# T-11_Version_6.net
KiCad netlist of a schematic drawn in EAGLE
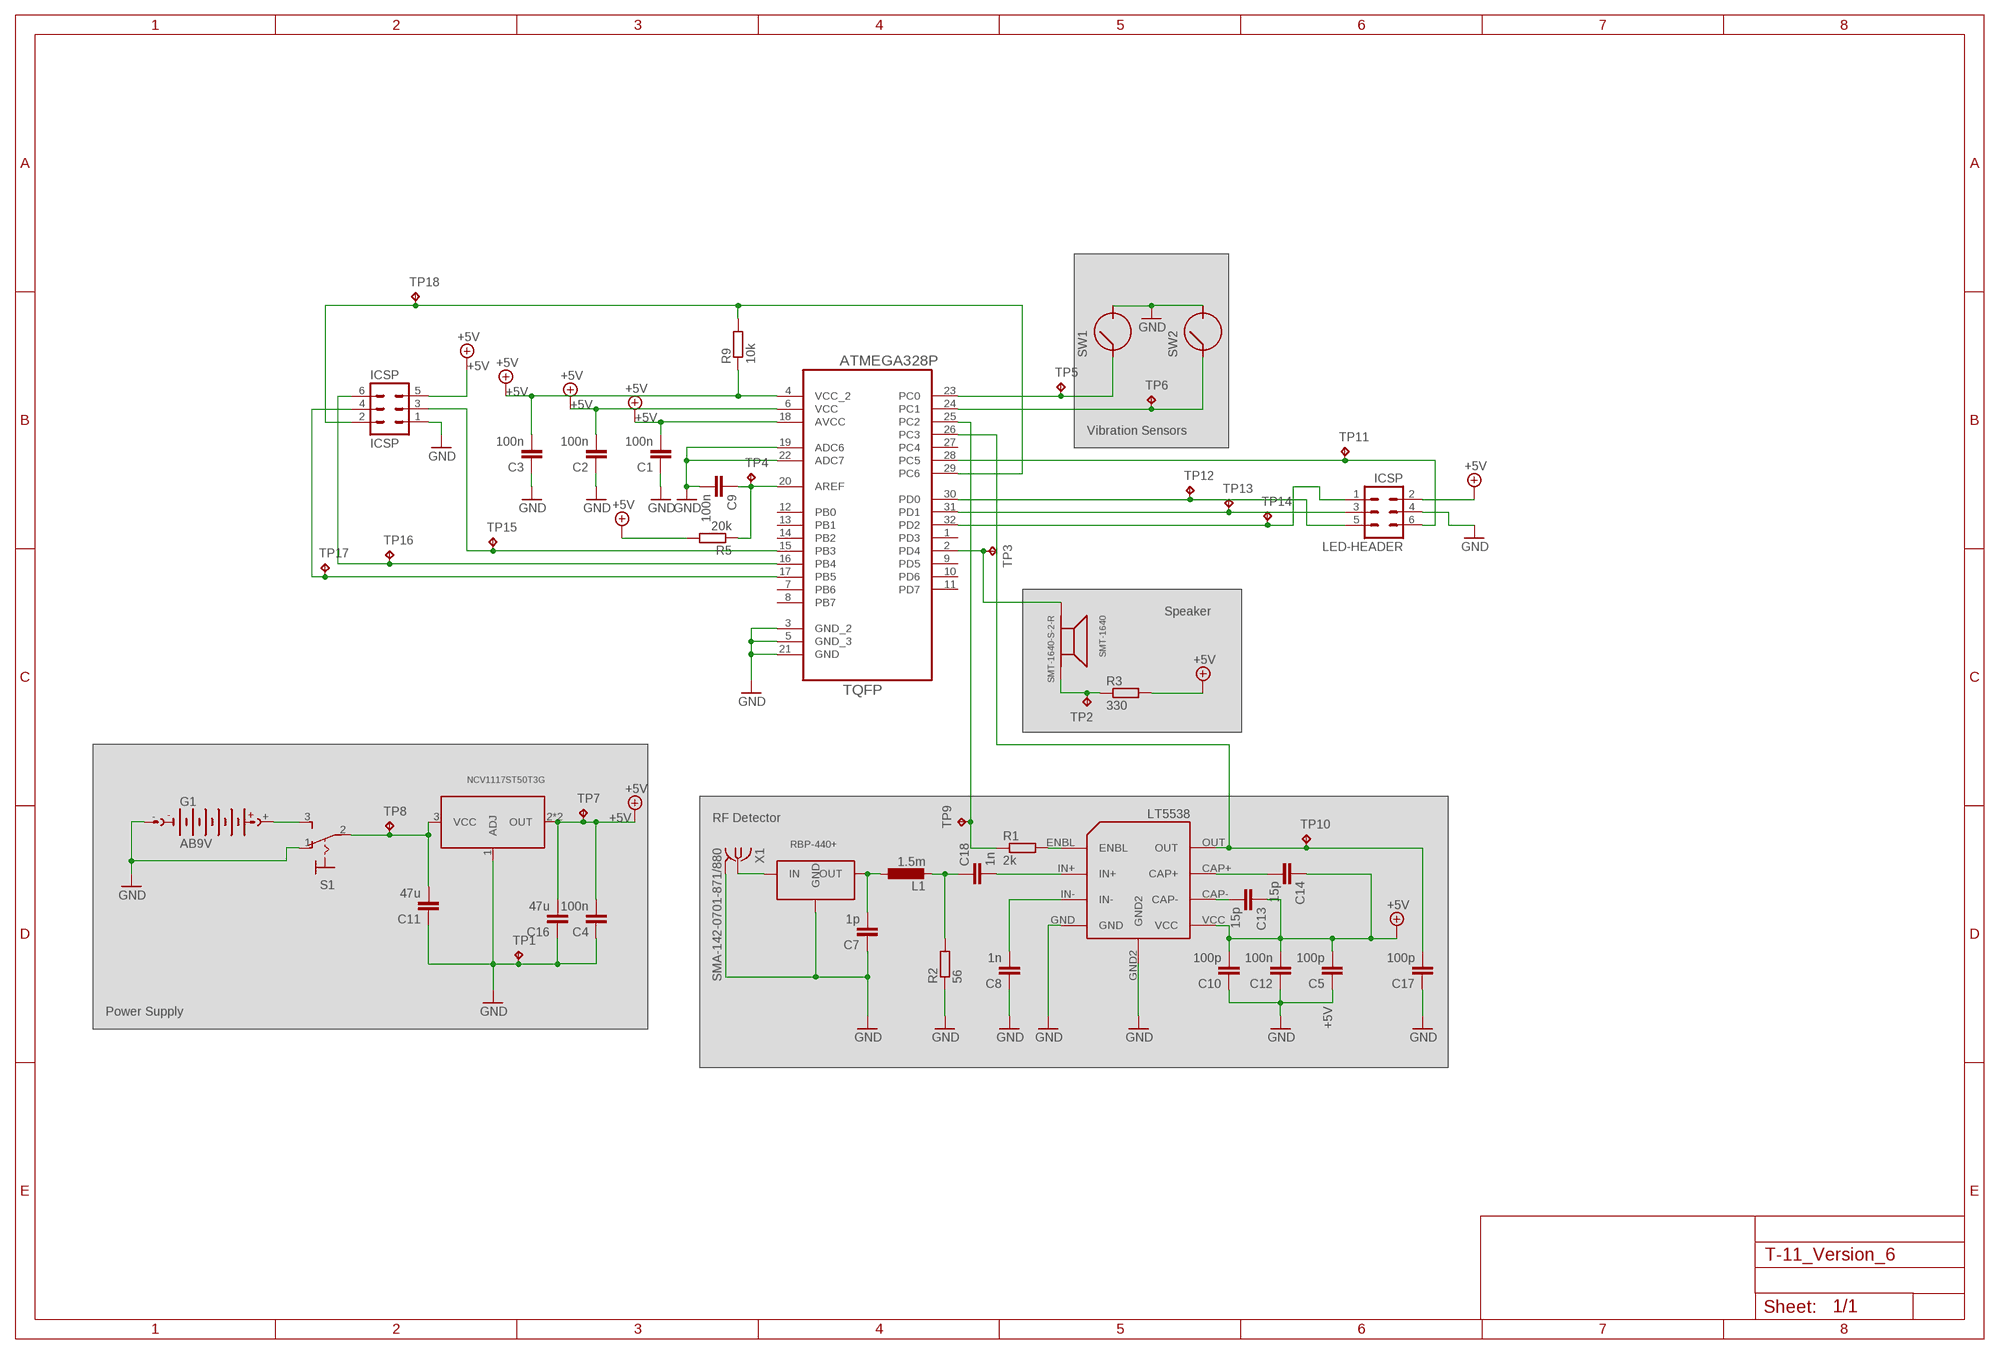
[diagram p0: schematic, sheet 1]

(export (version "E")
  (design (tool "Eeschema 10.0.6"))
  (components
    (comp (ref "C1")
      (value "100n")
      (footprint "eagle-import:C0805")
      (libsource (lib "eagle-import") (part "C-EUC0805"))
    )
    (comp (ref "C2")
      (value "100n")
      (footprint "eagle-import:C0805")
      (libsource (lib "eagle-import") (part "C-EUC0805"))
    )
    (comp (ref "C3")
      (value "100n")
      (footprint "eagle-import:C0805")
      (libsource (lib "eagle-import") (part "C-EUC0805"))
    )
    (comp (ref "C4")
      (value "100n")
      (footprint "eagle-import:C0805")
      (libsource (lib "eagle-import") (part "C-EUC0805"))
    )
    (comp (ref "C5")
      (value "100p")
      (footprint "eagle-import:C0805")
      (libsource (lib "eagle-import") (part "C-EUC0805"))
    )
    (comp (ref "C7")
      (value "1p")
      (footprint "eagle-import:C0805")
      (libsource (lib "eagle-import") (part "C-EUC0805"))
    )
    (comp (ref "C8")
      (value "1n")
      (footprint "eagle-import:C0805")
      (libsource (lib "eagle-import") (part "C-EUC0805"))
    )
    (comp (ref "C9")
      (value "100n")
      (footprint "eagle-import:C0805")
      (libsource (lib "eagle-import") (part "C-EUC0805"))
    )
    (comp (ref "C10")
      (value "100p")
      (footprint "eagle-import:C0805")
      (libsource (lib "eagle-import") (part "C-EUC0805"))
    )
    (comp (ref "C11")
      (value "47u")
      (footprint "eagle-import:C0805")
      (libsource (lib "eagle-import") (part "C-EUC0805"))
    )
    (comp (ref "C12")
      (value "100n")
      (footprint "eagle-import:C0805")
      (libsource (lib "eagle-import") (part "C-EUC0805"))
    )
    (comp (ref "C13")
      (value "15p")
      (footprint "eagle-import:C0805")
      (libsource (lib "eagle-import") (part "C-EUC0805"))
    )
    (comp (ref "C14")
      (value "15p")
      (footprint "eagle-import:C0805")
      (libsource (lib "eagle-import") (part "C-EUC0805"))
    )
    (comp (ref "C16")
      (value "47u")
      (footprint "eagle-import:C0805")
      (libsource (lib "eagle-import") (part "C-EUC0805"))
    )
    (comp (ref "C17")
      (value "100p")
      (footprint "eagle-import:C0805")
      (libsource (lib "eagle-import") (part "C-EUC0805"))
    )
    (comp (ref "C18")
      (value "1n")
      (footprint "eagle-import:C0805")
      (libsource (lib "eagle-import") (part "C-EUC0805"))
    )
    (comp (ref "G1")
      (value "AB9V")
      (footprint "eagle-import:AB9V")
      (libsource (lib "eagle-import") (part "AB9V"))
    )
    (comp (ref "ICSP")
      (value "ICSP")
      (footprint "eagle-import:MA03-2")
      (libsource (lib "eagle-import") (part "MA03-2"))
    )
    (comp (ref "L1")
      (value "1.5m")
      (footprint "eagle-import:L2825P")
      (libsource (lib "eagle-import") (part "L-EUL2825P"))
    )
    (comp (ref "LED-HEADER")
      (value "ICSP")
      (footprint "eagle-import:MA03-2")
      (libsource (lib "eagle-import") (part "MA03-2"))
    )
    (comp (ref "LT5538")
      (value "LT5538")
      (footprint "eagle-import:LT5538")
      (libsource (lib "eagle-import") (part "LT5538"))
    )
    (comp (ref "NVC1")
      (value "NCV1117ST50T3G")
      (footprint "eagle-import:SOT223")
      (libsource (lib "eagle-import") (part "NCV1117ST50T3G"))
    )
    (comp (ref "R1")
      (value "2k")
      (footprint "eagle-import:R0805")
      (libsource (lib "eagle-import") (part "R-EU_R0805"))
    )
    (comp (ref "R2")
      (value "56")
      (footprint "eagle-import:R0805")
      (libsource (lib "eagle-import") (part "R-EU_R0805"))
    )
    (comp (ref "R3")
      (value "330")
      (footprint "eagle-import:R0805")
      (libsource (lib "eagle-import") (part "R-EU_R0805"))
    )
    (comp (ref "R5")
      (value "20k")
      (footprint "eagle-import:R0805")
      (libsource (lib "eagle-import") (part "R-EU_R0805"))
    )
    (comp (ref "R9")
      (value "10k")
      (footprint "eagle-import:R0805")
      (libsource (lib "eagle-import") (part "R-EU_R0805"))
    )
    (comp (ref "RBP-440+")
      (value "RBP-440+")
      (footprint "eagle-import:GP731")
      (libsource (lib "eagle-import") (part "RBP-440+"))
    )
    (comp (ref "S1")
      (value "320-916")
      (footprint "eagle-import:320-916")
      (libsource (lib "eagle-import") (part "320-916"))
    )
    (comp (ref "SMT-1640")
      (value "SMT-1640-S-2-R")
      (footprint "eagle-import:SMT-1640")
      (libsource (lib "eagle-import") (part "SMT-1640-S-2-R"))
    )
    (comp (ref "SW1")
      (value "SW-1801X")
      (footprint "eagle-import:SW-1801X")
      (libsource (lib "eagle-import") (part "SW-1801X"))
    )
    (comp (ref "SW2")
      (value "SW-1801X")
      (footprint "eagle-import:SW-1801X")
      (libsource (lib "eagle-import") (part "SW-1801X"))
    )
    (comp (ref "TP1")
      (value "TPTP10R")
      (footprint "eagle-import:TP10R")
      (libsource (lib "eagle-import") (part "TPTP10R"))
    )
    (comp (ref "TP2")
      (value "TPTP10R")
      (footprint "eagle-import:TP10R")
      (libsource (lib "eagle-import") (part "TPTP10R"))
    )
    (comp (ref "TP3")
      (value "TPTP10R")
      (footprint "eagle-import:TP10R")
      (libsource (lib "eagle-import") (part "TPTP10R"))
    )
    (comp (ref "TP4")
      (value "TPTP10R")
      (footprint "eagle-import:TP10R")
      (libsource (lib "eagle-import") (part "TPTP10R"))
    )
    (comp (ref "TP5")
      (value "TPTP10R")
      (footprint "eagle-import:TP10R")
      (libsource (lib "eagle-import") (part "TPTP10R"))
    )
    (comp (ref "TP6")
      (value "TPTP10R")
      (footprint "eagle-import:TP10R")
      (libsource (lib "eagle-import") (part "TPTP10R"))
    )
    (comp (ref "TP7")
      (value "TPTP10R")
      (footprint "eagle-import:TP10R")
      (libsource (lib "eagle-import") (part "TPTP10R"))
    )
    (comp (ref "TP8")
      (value "TPTP10R")
      (footprint "eagle-import:TP10R")
      (libsource (lib "eagle-import") (part "TPTP10R"))
    )
    (comp (ref "TP9")
      (value "TPTP10R")
      (footprint "eagle-import:TP10R")
      (libsource (lib "eagle-import") (part "TPTP10R"))
    )
    (comp (ref "TP10")
      (value "TPTP10R")
      (footprint "eagle-import:TP10R")
      (libsource (lib "eagle-import") (part "TPTP10R"))
    )
    (comp (ref "TP11")
      (value "TPTP10R")
      (footprint "eagle-import:TP10R")
      (libsource (lib "eagle-import") (part "TPTP10R"))
    )
    (comp (ref "TP12")
      (value "TPTP10R")
      (footprint "eagle-import:TP10R")
      (libsource (lib "eagle-import") (part "TPTP10R"))
    )
    (comp (ref "TP13")
      (value "TPTP10R")
      (footprint "eagle-import:TP10R")
      (libsource (lib "eagle-import") (part "TPTP10R"))
    )
    (comp (ref "TP14")
      (value "TPTP10R")
      (footprint "eagle-import:TP10R")
      (libsource (lib "eagle-import") (part "TPTP10R"))
    )
    (comp (ref "TP15")
      (value "TPTP10R")
      (footprint "eagle-import:TP10R")
      (libsource (lib "eagle-import") (part "TPTP10R"))
    )
    (comp (ref "TP16")
      (value "TPTP10R")
      (footprint "eagle-import:TP10R")
      (libsource (lib "eagle-import") (part "TPTP10R"))
    )
    (comp (ref "TP17")
      (value "TPTP10R")
      (footprint "eagle-import:TP10R")
      (libsource (lib "eagle-import") (part "TPTP10R"))
    )
    (comp (ref "TP18")
      (value "TPTP10R")
      (footprint "eagle-import:TP10R")
      (libsource (lib "eagle-import") (part "TPTP10R"))
    )
    (comp (ref "U1")
      (value "ATMEGA328P-AU")
      (footprint "eagle-import:QFP80P900X900X120-32N")
      (libsource (lib "eagle-import") (part "ATMEGA328P-AU"))
    )
    (comp (ref "X1")
      (value "SMA-142-0701-871/880")
      (footprint "eagle-import:SMA-142-0701-871")
      (fields (field (name "MF") "JOHNSON COMPONENTS") (field (name "MPN") "142-0701-871"))
      (libsource (lib "eagle-import") (part "SMA-142-0701-871/880"))
    )
  )
  (nets
    (net (code "1") (name "+5V") (class "Default")
      (node (ref "C1") (pin "2") (pinfunction "2_2") (pintype "passive"))
      (node (ref "C10") (pin "2") (pinfunction "2_2") (pintype "passive"))
      (node (ref "C12") (pin "2") (pinfunction "2_2") (pintype "passive"))
      (node (ref "C13") (pin "1") (pinfunction "1_1") (pintype "passive"))
      (node (ref "C14") (pin "1") (pinfunction "1_1") (pintype "passive"))
      (node (ref "C16") (pin "2") (pinfunction "2_2") (pintype "passive"))
      (node (ref "C2") (pin "2") (pinfunction "2_2") (pintype "passive"))
      (node (ref "C3") (pin "2") (pinfunction "2_2") (pintype "passive"))
      (node (ref "C4") (pin "2") (pinfunction "2_2") (pintype "passive"))
      (node (ref "C5") (pin "2") (pinfunction "2_2") (pintype "passive"))
      (node (ref "ICSP") (pin "5") (pinfunction "5_5") (pintype "passive"))
      (node (ref "LED-HEADER") (pin "2") (pinfunction "2_2") (pintype "passive"))
      (node (ref "LT5538") (pin "VCC") (pinfunction "VCC_VCC") (pintype "power_in"))
      (node (ref "NVC1") (pin "2") (pinfunction "OUT_2") (pintype "power_in"))
      (node (ref "NVC1") (pin "4") (pinfunction "OUT_4") (pintype "power_in"))
      (node (ref "R3") (pin "2") (pinfunction "2_2") (pintype "passive"))
      (node (ref "R5") (pin "2") (pinfunction "2_2") (pintype "passive"))
      (node (ref "R9") (pin "1") (pinfunction "1_1") (pintype "passive"))
      (node (ref "TP7") (pin "TP") (pinfunction "TP_TP") (pintype "input"))
      (node (ref "U1") (pin "18") (pinfunction "AVCC_18") (pintype "power_in"))
      (node (ref "U1") (pin "4") (pinfunction "VCC_2_4") (pintype "power_in"))
      (node (ref "U1") (pin "6") (pinfunction "VCC_6") (pintype "power_in"))
    )
    (net (code "2") (name "GND") (class "Default")
      (node (ref "C1") (pin "1") (pinfunction "1_1") (pintype "passive"))
      (node (ref "C10") (pin "1") (pinfunction "1_1") (pintype "passive"))
      (node (ref "C11") (pin "1") (pinfunction "1_1") (pintype "passive"))
      (node (ref "C12") (pin "1") (pinfunction "1_1") (pintype "passive"))
      (node (ref "C16") (pin "1") (pinfunction "1_1") (pintype "passive"))
      (node (ref "C17") (pin "1") (pinfunction "1_1") (pintype "passive"))
      (node (ref "C2") (pin "1") (pinfunction "1_1") (pintype "passive"))
      (node (ref "C3") (pin "1") (pinfunction "1_1") (pintype "passive"))
      (node (ref "C4") (pin "1") (pinfunction "1_1") (pintype "passive"))
      (node (ref "C5") (pin "1") (pinfunction "1_1") (pintype "passive"))
      (node (ref "C7") (pin "1") (pinfunction "1_1") (pintype "passive"))
      (node (ref "C8") (pin "1") (pinfunction "1_1") (pintype "passive"))
      (node (ref "C9") (pin "2") (pinfunction "2_2") (pintype "passive"))
      (node (ref "G1") (pin "-") (pinfunction "-_-") (pintype "passive"))
      (node (ref "ICSP") (pin "1") (pinfunction "1_1") (pintype "passive"))
      (node (ref "LED-HEADER") (pin "4") (pinfunction "4_4") (pintype "passive"))
      (node (ref "LT5538") (pin "GND") (pinfunction "GND_GND") (pintype "power_in"))
      (node (ref "LT5538") (pin "GND2") (pinfunction "GND2_GND2") (pintype "bidirectional"))
      (node (ref "NVC1") (pin "1") (pinfunction "ADJ_1") (pintype "bidirectional"))
      (node (ref "R2") (pin "1") (pinfunction "1_1") (pintype "passive"))
      (node (ref "RBP-440+") (pin "1") (pinfunction "GND_1") (pintype "output"))
      (node (ref "RBP-440+") (pin "3") (pinfunction "GND_3") (pintype "output"))
      (node (ref "RBP-440+") (pin "4") (pinfunction "GND_4") (pintype "output"))
      (node (ref "RBP-440+") (pin "5") (pinfunction "GND_5") (pintype "output"))
      (node (ref "RBP-440+") (pin "7") (pinfunction "GND_7") (pintype "output"))
      (node (ref "RBP-440+") (pin "8") (pinfunction "GND_8") (pintype "output"))
      (node (ref "S1") (pin "1") (pinfunction "O_1") (pintype "passive"))
      (node (ref "SW1") (pin "P$2") (pinfunction "P$2_P$2") (pintype "bidirectional"))
      (node (ref "SW2") (pin "P$2") (pinfunction "P$2_P$2") (pintype "bidirectional"))
      (node (ref "TP1") (pin "TP") (pinfunction "TP_TP") (pintype "input"))
      (node (ref "U1") (pin "19") (pinfunction "ADC6_19") (pintype "input"))
      (node (ref "U1") (pin "21") (pinfunction "GND_21") (pintype "passive"))
      (node (ref "U1") (pin "22") (pinfunction "ADC7_22") (pintype "input"))
      (node (ref "U1") (pin "3") (pinfunction "GND_2_3") (pintype "passive"))
      (node (ref "U1") (pin "5") (pinfunction "GND_3_5") (pintype "passive"))
      (node (ref "X1") (pin "2@1") (pinfunction "2_2@1") (pintype "passive"))
      (node (ref "X1") (pin "2@2") (pinfunction "2_2@2") (pintype "passive"))
      (node (ref "X1") (pin "2@3") (pinfunction "2_2@3") (pintype "passive"))
      (node (ref "X1") (pin "2@4") (pinfunction "2_2@4") (pintype "passive"))
    )
    (net (code "3") (name "Net-(C8-Pad2)") (class "Default")
      (node (ref "C8") (pin "2") (pinfunction "2_2") (pintype "passive"))
      (node (ref "LT5538") (pin "IN-") (pinfunction "IN-_IN-") (pintype "bidirectional"))
    )
    (net (code "4") (name "Net-(C13-Pad2)") (class "Default")
      (node (ref "C13") (pin "2") (pinfunction "2_2") (pintype "passive"))
      (node (ref "LT5538") (pin "CAP-") (pinfunction "CAP-_CAP-") (pintype "bidirectional"))
    )
    (net (code "5") (name "Net-(C14-Pad2)") (class "Default")
      (node (ref "C14") (pin "2") (pinfunction "2_2") (pintype "passive"))
      (node (ref "LT5538") (pin "CAP+") (pinfunction "CAP+_CAP+") (pintype "bidirectional"))
    )
    (net (code "6") (name "Net-(C18-Pad1)") (class "Default")
      (node (ref "C18") (pin "1") (pinfunction "1_1") (pintype "passive"))
      (node (ref "L1") (pin "2") (pinfunction "2_2") (pintype "passive"))
      (node (ref "R2") (pin "2") (pinfunction "2_2") (pintype "passive"))
    )
    (net (code "7") (name "Net-(C18-Pad2)") (class "Default")
      (node (ref "C18") (pin "2") (pinfunction "2_2") (pintype "passive"))
      (node (ref "LT5538") (pin "IN+") (pinfunction "IN+_IN+") (pintype "bidirectional"))
    )
    (net (code "8") (name "Net-(LT5538-PadENBL)") (class "Default")
      (node (ref "LT5538") (pin "ENBL") (pinfunction "ENBL_ENBL") (pintype "bidirectional"))
      (node (ref "R1") (pin "2") (pinfunction "2_2") (pintype "passive"))
    )
    (net (code "9") (name "Net-(NVC1-VCC)") (class "Default")
      (node (ref "C11") (pin "2") (pinfunction "2_2") (pintype "passive"))
      (node (ref "NVC1") (pin "3") (pinfunction "VCC_3") (pintype "input"))
      (node (ref "S1") (pin "2") (pinfunction "P_2") (pintype "passive"))
      (node (ref "TP8") (pin "TP") (pinfunction "TP_TP") (pintype "input"))
    )
    (net (code "10") (name "Net-(RBP-440+-IN)") (class "Default")
      (node (ref "RBP-440+") (pin "2") (pinfunction "IN_2") (pintype "bidirectional"))
      (node (ref "X1") (pin "1") (pinfunction "1_1") (pintype "passive"))
    )
    (net (code "11") (name "Net-(RBP-440+-OUT)") (class "Default")
      (node (ref "C7") (pin "2") (pinfunction "2_2") (pintype "passive"))
      (node (ref "L1") (pin "1") (pinfunction "1_1") (pintype "passive"))
      (node (ref "RBP-440+") (pin "6") (pinfunction "OUT_6") (pintype "output"))
    )
    (net (code "12") (name "Net-(S1-S)") (class "Default")
      (node (ref "G1") (pin "+") (pinfunction "+_+") (pintype "passive"))
      (node (ref "S1") (pin "3") (pinfunction "S_3") (pintype "passive"))
    )
    (net (code "13") (name "Net-(SMT-1640-IN)") (class "Default")
      (node (ref "SMT-1640") (pin "P$2") (pinfunction "IN_P$2") (pintype "bidirectional"))
      (node (ref "TP3") (pin "TP") (pinfunction "TP_TP") (pintype "input"))
      (node (ref "U1") (pin "2") (pinfunction "PD4_2") (pintype "bidirectional"))
    )
    (net (code "14") (name "Net-(SMT-1640-OUT)") (class "Default")
      (node (ref "R3") (pin "1") (pinfunction "1_1") (pintype "passive"))
      (node (ref "SMT-1640") (pin "P$1") (pinfunction "OUT_P$1") (pintype "bidirectional"))
      (node (ref "TP2") (pin "TP") (pinfunction "TP_TP") (pintype "input"))
    )
    (net (code "15") (name "Net-(U1-AREF)") (class "Default")
      (node (ref "C9") (pin "1") (pinfunction "1_1") (pintype "passive"))
      (node (ref "R5") (pin "1") (pinfunction "1_1") (pintype "passive"))
      (node (ref "TP4") (pin "TP") (pinfunction "TP_TP") (pintype "input"))
      (node (ref "U1") (pin "20") (pinfunction "AREF_20") (pintype "input"))
    )
    (net (code "16") (name "Net-(U1-PB3)") (class "Default")
      (node (ref "ICSP") (pin "3") (pinfunction "3_3") (pintype "passive"))
      (node (ref "TP15") (pin "TP") (pinfunction "TP_TP") (pintype "input"))
      (node (ref "U1") (pin "15") (pinfunction "PB3_15") (pintype "bidirectional"))
    )
    (net (code "17") (name "Net-(U1-PB4)") (class "Default")
      (node (ref "ICSP") (pin "6") (pinfunction "6_6") (pintype "passive"))
      (node (ref "TP16") (pin "TP") (pinfunction "TP_TP") (pintype "input"))
      (node (ref "U1") (pin "16") (pinfunction "PB4_16") (pintype "bidirectional"))
    )
    (net (code "18") (name "Net-(U1-PB5)") (class "Default")
      (node (ref "ICSP") (pin "4") (pinfunction "4_4") (pintype "passive"))
      (node (ref "TP17") (pin "TP") (pinfunction "TP_TP") (pintype "input"))
      (node (ref "U1") (pin "17") (pinfunction "PB5_17") (pintype "bidirectional"))
    )
    (net (code "19") (name "Net-(U1-PC0)") (class "Default")
      (node (ref "SW1") (pin "P$1") (pinfunction "P$1_P$1") (pintype "bidirectional"))
      (node (ref "TP5") (pin "TP") (pinfunction "TP_TP") (pintype "input"))
      (node (ref "U1") (pin "23") (pinfunction "PC0_23") (pintype "bidirectional"))
    )
    (net (code "20") (name "Net-(U1-PC1)") (class "Default")
      (node (ref "SW2") (pin "P$1") (pinfunction "P$1_P$1") (pintype "bidirectional"))
      (node (ref "TP6") (pin "TP") (pinfunction "TP_TP") (pintype "input"))
      (node (ref "U1") (pin "24") (pinfunction "PC1_24") (pintype "bidirectional"))
    )
    (net (code "21") (name "Net-(U1-PC2)") (class "Default")
      (node (ref "R1") (pin "1") (pinfunction "1_1") (pintype "passive"))
      (node (ref "TP9") (pin "TP") (pinfunction "TP_TP") (pintype "input"))
      (node (ref "U1") (pin "25") (pinfunction "PC2_25") (pintype "bidirectional"))
    )
    (net (code "22") (name "Net-(U1-PC3)") (class "Default")
      (node (ref "C17") (pin "2") (pinfunction "2_2") (pintype "passive"))
      (node (ref "LT5538") (pin "OUT") (pinfunction "OUT_OUT") (pintype "output"))
      (node (ref "TP10") (pin "TP") (pinfunction "TP_TP") (pintype "input"))
      (node (ref "U1") (pin "26") (pinfunction "PC3_26") (pintype "bidirectional"))
    )
    (net (code "23") (name "Net-(U1-PC5)") (class "Default")
      (node (ref "LED-HEADER") (pin "6") (pinfunction "6_6") (pintype "passive"))
      (node (ref "TP11") (pin "TP") (pinfunction "TP_TP") (pintype "input"))
      (node (ref "U1") (pin "28") (pinfunction "PC5_28") (pintype "bidirectional"))
    )
    (net (code "24") (name "Net-(U1-PC6)") (class "Default")
      (node (ref "ICSP") (pin "2") (pinfunction "2_2") (pintype "passive"))
      (node (ref "R9") (pin "2") (pinfunction "2_2") (pintype "passive"))
      (node (ref "TP18") (pin "TP") (pinfunction "TP_TP") (pintype "input"))
      (node (ref "U1") (pin "29") (pinfunction "PC6_29") (pintype "bidirectional"))
    )
    (net (code "25") (name "Net-(U1-PD0)") (class "Default")
      (node (ref "LED-HEADER") (pin "5") (pinfunction "5_5") (pintype "passive"))
      (node (ref "TP12") (pin "TP") (pinfunction "TP_TP") (pintype "input"))
      (node (ref "U1") (pin "30") (pinfunction "PD0_30") (pintype "bidirectional"))
    )
    (net (code "26") (name "Net-(U1-PD1)") (class "Default")
      (node (ref "LED-HEADER") (pin "3") (pinfunction "3_3") (pintype "passive"))
      (node (ref "TP13") (pin "TP") (pinfunction "TP_TP") (pintype "input"))
      (node (ref "U1") (pin "31") (pinfunction "PD1_31") (pintype "bidirectional"))
    )
    (net (code "27") (name "Net-(U1-PD2)") (class "Default")
      (node (ref "LED-HEADER") (pin "1") (pinfunction "1_1") (pintype "passive"))
      (node (ref "TP14") (pin "TP") (pinfunction "TP_TP") (pintype "input"))
      (node (ref "U1") (pin "32") (pinfunction "PD2_32") (pintype "bidirectional"))
    )
    (net (code "28") (name "unconnected-(U1-PB0-Pad12)") (class "Default")
      (node (ref "U1") (pin "12") (pinfunction "PB0_12") (pintype "bidirectional"))
    )
    (net (code "29") (name "unconnected-(U1-PB1-Pad13)") (class "Default")
      (node (ref "U1") (pin "13") (pinfunction "PB1_13") (pintype "bidirectional"))
    )
    (net (code "30") (name "unconnected-(U1-PB2-Pad14)") (class "Default")
      (node (ref "U1") (pin "14") (pinfunction "PB2_14") (pintype "bidirectional"))
    )
    (net (code "31") (name "unconnected-(U1-PB6-Pad7)") (class "Default")
      (node (ref "U1") (pin "7") (pinfunction "PB6_7") (pintype "bidirectional"))
    )
    (net (code "32") (name "unconnected-(U1-PB7-Pad8)") (class "Default")
      (node (ref "U1") (pin "8") (pinfunction "PB7_8") (pintype "bidirectional"))
    )
    (net (code "33") (name "unconnected-(U1-PC4-Pad27)") (class "Default")
      (node (ref "U1") (pin "27") (pinfunction "PC4_27") (pintype "bidirectional"))
    )
    (net (code "34") (name "unconnected-(U1-PD3-Pad1)") (class "Default")
      (node (ref "U1") (pin "1") (pinfunction "PD3_1") (pintype "bidirectional"))
    )
    (net (code "35") (name "unconnected-(U1-PD5-Pad9)") (class "Default")
      (node (ref "U1") (pin "9") (pinfunction "PD5_9") (pintype "bidirectional"))
    )
    (net (code "36") (name "unconnected-(U1-PD6-Pad10)") (class "Default")
      (node (ref "U1") (pin "10") (pinfunction "PD6_10") (pintype "bidirectional"))
    )
    (net (code "37") (name "unconnected-(U1-PD7-Pad11)") (class "Default")
      (node (ref "U1") (pin "11") (pinfunction "PD7_11") (pintype "bidirectional"))
    )
  )
)
